# 2_usb.net
KiCad netlist of a schematic drawn in Altium Designer
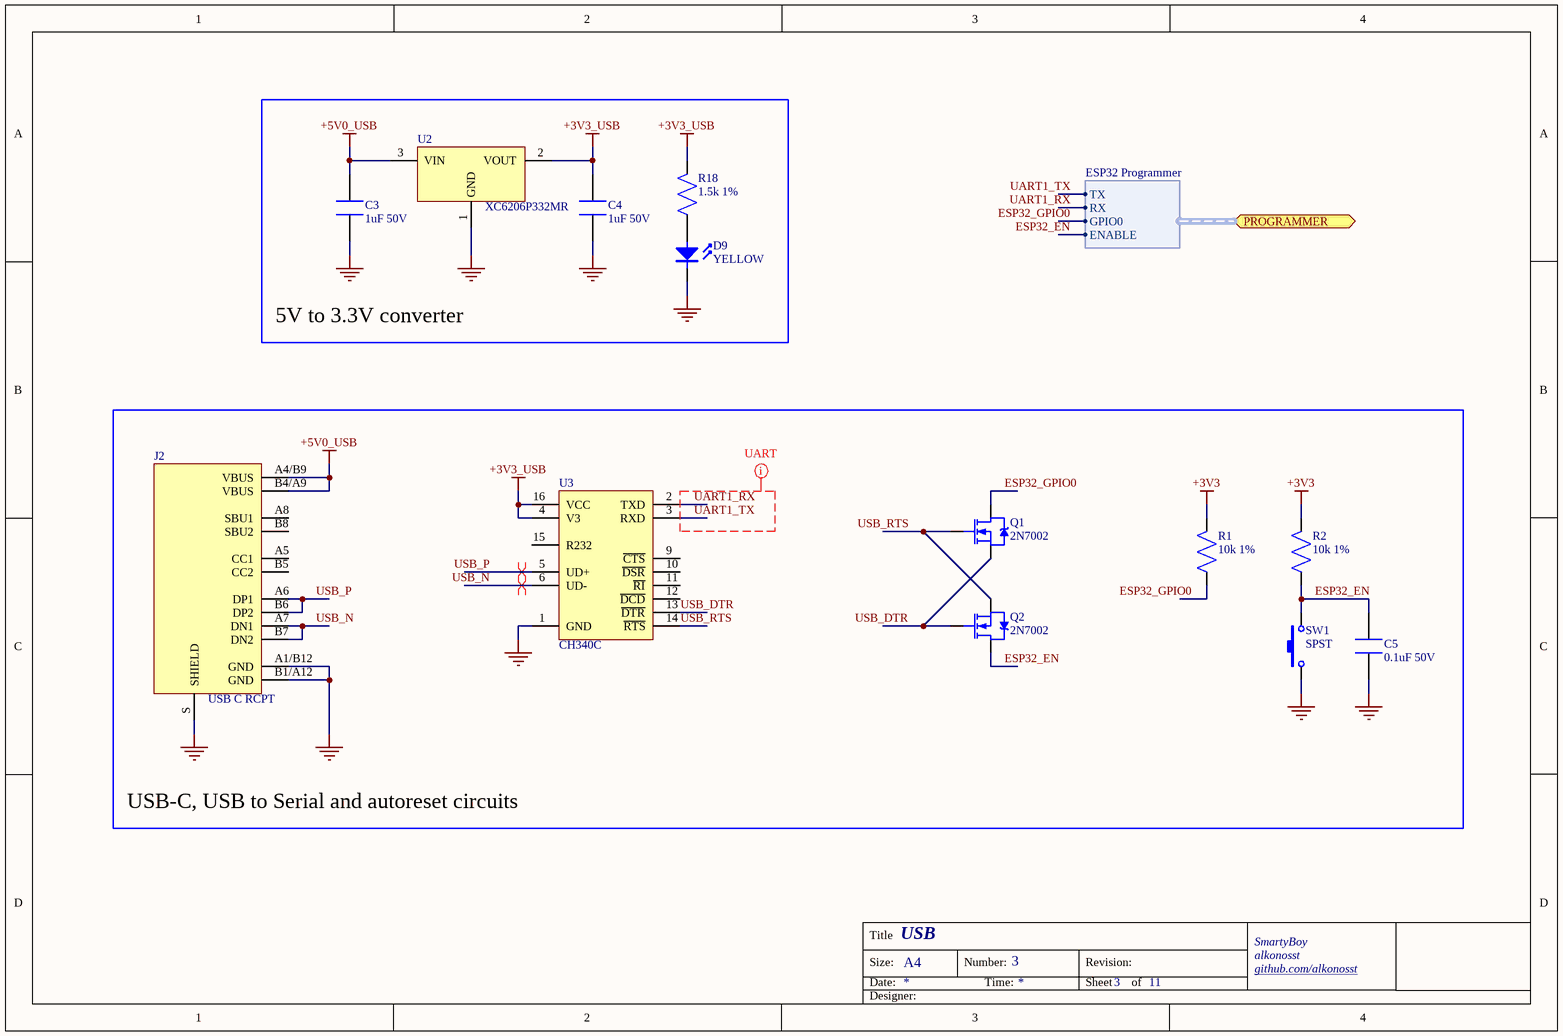
[diagram p0: 2_usb.SchDoc]

(export (version "E")
  (design (tool "Eeschema 10.0.6"))
  (components
    (comp (ref "C3")
      (value "1uF 50V")
      (footprint "C0603")
      (description "X5R ±10% 50V 1uF 0603 Multilayer Ceramic Capacitors MLCC - SMD/SMT")
      (fields (field (name "LCSC PART") "C15849"))
      (libsource (lib "nombre_por_definir") (part "CL10A105KB8NNNC"))
    )
    (comp (ref "C4")
      (value "1uF 50V")
      (footprint "C0603")
      (description "X5R ±10% 50V 1uF 0603 Multilayer Ceramic Capacitors MLCC - SMD/SMT")
      (fields (field (name "LCSC PART") "C15849"))
      (libsource (lib "nombre_por_definir") (part "CL10A105KB8NNNC"))
    )
    (comp (ref "C5")
      (value "0.1uF 50V")
      (footprint "C0603")
      (description "X7R 100nF ±10% 50V 0603 Multilayer Ceramic Capacitors MLCC - SMD/SMT")
      (fields (field (name "LCSC PART") "C14663"))
      (libsource (lib "nombre_por_definir") (part "CC0603KRX7R9BB104"))
    )
    (comp (ref "D9")
      (value "YELLOW")
      (footprint "LED0603-YELLOW")
      (description "Yellow 585.5~591.5nm 0603 Light Emitting Diodes (LED)")
      (fields (field (name "LCSC PART") "C72038"))
      (libsource (lib "nombre_por_definir") (part "19-213/Y2C-CQ2R2L/3T(CY)"))
    )
    (comp (ref "J2")
      (value "USB C RCPT")
      (footprint "USB-TYPE-C-RCPT")
      (description "Receptacle USB Type C 16 Pins")
      (fields (field (name "LCSC PART") "C165948"))
      (libsource (lib "nombre_por_definir") (part "TYPE-C-31-M-12"))
    )
    (comp (ref "Q1")
      (value "2N7002")
      (footprint "SOT-23-3")
      (description "2.5V 250uA 0.115A 60V N Channel 7.5Ω 500mA,10V 0.2W SOT-23(SOT-23-3) MOSFETs")
      (fields (field (name "LCSC PART") "C8545"))
      (libsource (lib "nombre_por_definir") (part "2N7002"))
    )
    (comp (ref "Q2")
      (value "2N7002")
      (footprint "SOT-23-3")
      (description "2.5V 250uA 0.115A 60V N Channel 7.5Ω 500mA,10V 0.2W SOT-23(SOT-23-3) MOSFETs")
      (fields (field (name "LCSC PART") "C8545"))
      (libsource (lib "nombre_por_definir") (part "2N7002"))
    )
    (comp (ref "R1")
      (value "10k 1%")
      (footprint "R0603")
      (description "±1% ±100ppm/℃ 10kΩ 0.1W 0603 Chip Resistor - Surface Mount")
      (fields (field (name "LCSC PART") "C25804"))
      (libsource (lib "nombre_por_definir") (part "0603WAF1002T5E"))
    )
    (comp (ref "R2")
      (value "10k 1%")
      (footprint "R0603")
      (description "±1% ±100ppm/℃ 10kΩ 0.1W 0603 Chip Resistor - Surface Mount")
      (fields (field (name "LCSC PART") "C25804"))
      (libsource (lib "nombre_por_definir") (part "0603WAF1002T5E"))
    )
    (comp (ref "R18")
      (value "1.5k 1%")
      (footprint "R0603")
      (description "1.5kΩ ±1% ±100ppm/℃ 0.1W 0603 Chip Resistor - Surface Mount")
      (fields (field (name "LCSC PART") "C22843"))
      (libsource (lib "nombre_por_definir") (part "0603WAF1501T5E"))
    )
    (comp (ref "SW1")
      (value "SPST")
      (footprint "SW-TS-1187A-B-A-B")
      (description "Top Actuated 50mA @ 12VDC Round Button 160gf SPST SMD Tactile Switches")
      (fields (field (name "LCSC PART") "C318884"))
      (libsource (lib "nombre_por_definir") (part "TS-1187A-B-A-B"))
    )
    (comp (ref "U2")
      (value "XC6206P332MR")
      (footprint "SOT-23-3")
      (description "6V 680mV @ 100mA Fixed 3.3V SOT-23-3L Linear Voltage Regulators (LDO)")
      (fields (field (name "LCSC PART") "C5446"))
      (libsource (lib "nombre_por_definir") (part "XC6206P332MR"))
    )
    (comp (ref "U3")
      (value "CH340C")
      (footprint "SOP-16")
      (description "USB 2.0 Transceiver 2Mbps SOP-16_150mil USB ICs ROHS")
      (fields (field (name "LCSC PART") "C84681"))
      (libsource (lib "nombre_por_definir") (part "CH340C"))
    )
  )
  (nets
    (net (code "3") (name "+3V3") (class "Default")
      (node (ref "R1") (pin "2") (pinfunction "2_2") (pintype "passive"))
      (node (ref "R2") (pin "2") (pinfunction "2_2") (pintype "passive"))
    )
    (net (code "4") (name "+3V3_USB") (class "Default")
      (node (ref "C4") (pin "1") (pinfunction "1_1") (pintype "passive"))
      (node (ref "R18") (pin "2") (pinfunction "2_2") (pintype "passive"))
      (node (ref "U2") (pin "2") (pinfunction "VOUT_2") (pintype "passive"))
      (node (ref "U3") (pin "16") (pinfunction "VCC_16") (pintype "passive"))
      (node (ref "U3") (pin "4") (pinfunction "V3_4") (pintype "passive"))
    )
    (net (code "5") (name "+5V0_USB") (class "Default")
      (node (ref "C3") (pin "1") (pinfunction "1_1") (pintype "passive"))
      (node (ref "J2") (pin "A4/B9") (pinfunction "VBUS_A4/B9") (pintype "passive"))
      (node (ref "J2") (pin "B4/A9") (pinfunction "VBUS_B4/A9") (pintype "passive"))
      (node (ref "U2") (pin "3") (pinfunction "VIN_3") (pintype "passive"))
    )
    (net (code "6") (name "/ESP32_EN") (class "Default")
      (node (ref "C5") (pin "1") (pinfunction "1_1") (pintype "passive"))
      (node (ref "Q2") (pin "3") (pinfunction "D_3") (pintype "passive"))
      (node (ref "R2") (pin "1") (pinfunction "1_1") (pintype "passive"))
      (node (ref "SW1") (pin "2") (pinfunction "2_2") (pintype "passive"))
    )
    (net (code "7") (name "/ESP32_GPIO0") (class "Default")
      (node (ref "Q1") (pin "3") (pinfunction "D_3") (pintype "passive"))
      (node (ref "R1") (pin "1") (pinfunction "1_1") (pintype "passive"))
    )
    (net (code "8") (name "/UART1_RX") (class "Default")
      (node (ref "U3") (pin "2") (pinfunction "TXD_2") (pintype "passive"))
    )
    (net (code "9") (name "/UART1_TX") (class "Default")
      (node (ref "U3") (pin "3") (pinfunction "RXD_3") (pintype "passive"))
    )
    (net (code "10") (name "/USB_DTR") (class "Default")
      (node (ref "Q1") (pin "2") (pinfunction "S_2") (pintype "passive"))
      (node (ref "Q2") (pin "1") (pinfunction "G_1") (pintype "passive"))
      (node (ref "U3") (pin "13") (pinfunction "~{DTR}_13") (pintype "passive"))
    )
    (net (code "11") (name "/USB_N") (class "Default")
      (node (ref "J2") (pin "A7") (pinfunction "DN1_A7") (pintype "passive"))
      (node (ref "J2") (pin "B7") (pinfunction "DN2_B7") (pintype "passive"))
      (node (ref "U3") (pin "6") (pinfunction "UD-_6") (pintype "passive"))
    )
    (net (code "12") (name "/USB_P") (class "Default")
      (node (ref "J2") (pin "A6") (pinfunction "DP1_A6") (pintype "passive"))
      (node (ref "J2") (pin "B6") (pinfunction "DP2_B6") (pintype "passive"))
      (node (ref "U3") (pin "5") (pinfunction "UD+_5") (pintype "passive"))
    )
    (net (code "13") (name "/USB_RTS") (class "Default")
      (node (ref "Q1") (pin "1") (pinfunction "G_1") (pintype "passive"))
      (node (ref "Q2") (pin "2") (pinfunction "S_2") (pintype "passive"))
      (node (ref "U3") (pin "14") (pinfunction "~{RTS}_14") (pintype "passive"))
    )
    (net (code "15") (name "GND") (class "Default")
      (node (ref "C3") (pin "2") (pinfunction "2_2") (pintype "passive"))
      (node (ref "C4") (pin "2") (pinfunction "2_2") (pintype "passive"))
      (node (ref "C5") (pin "2") (pinfunction "2_2") (pintype "passive"))
      (node (ref "D9") (pin "1") (pinfunction "1_1") (pintype "passive"))
      (node (ref "J2") (pin "A1/B12") (pinfunction "GND_A1/B12") (pintype "passive"))
      (node (ref "J2") (pin "B1/A12") (pinfunction "GND_B1/A12") (pintype "passive"))
      (node (ref "J2") (pin "S") (pinfunction "SHIELD_S") (pintype "passive"))
      (node (ref "SW1") (pin "1") (pinfunction "1_1") (pintype "passive"))
      (node (ref "U2") (pin "1") (pinfunction "GND_1") (pintype "passive"))
      (node (ref "U3") (pin "1") (pinfunction "GND_1") (pintype "passive"))
    )
    (net (code "16") (name "Net-(D9-Pad2)") (class "Default")
      (node (ref "D9") (pin "2") (pinfunction "2_2") (pintype "passive"))
      (node (ref "R18") (pin "1") (pinfunction "1_1") (pintype "passive"))
    )
    (net (code "17") (name "unconnected-(J2-CC1-PadA5)") (class "Default")
      (node (ref "J2") (pin "A5") (pinfunction "CC1_A5") (pintype "passive"))
    )
    (net (code "18") (name "unconnected-(J2-CC2-PadB5)") (class "Default")
      (node (ref "J2") (pin "B5") (pinfunction "CC2_B5") (pintype "passive"))
    )
    (net (code "19") (name "unconnected-(J2-SBU1-PadA8)") (class "Default")
      (node (ref "J2") (pin "A8") (pinfunction "SBU1_A8") (pintype "passive"))
    )
    (net (code "20") (name "unconnected-(J2-SBU2-PadB8)") (class "Default")
      (node (ref "J2") (pin "B8") (pinfunction "SBU2_B8") (pintype "passive"))
    )
    (net (code "21") (name "unconnected-(U3-NC1-Pad7)") (class "Default")
      (node (ref "U3") (pin "7") (pinfunction "NC1_7") (pintype "passive"))
    )
    (net (code "22") (name "unconnected-(U3-NC2-Pad8)") (class "Default")
      (node (ref "U3") (pin "8") (pinfunction "NC2_8") (pintype "passive"))
    )
    (net (code "23") (name "unconnected-(U3-R232-Pad15)") (class "Default")
      (node (ref "U3") (pin "15") (pinfunction "R232_15") (pintype "passive"))
    )
    (net (code "24") (name "unconnected-(U3-~{CTS}-Pad9)") (class "Default")
      (node (ref "U3") (pin "9") (pinfunction "~{CTS}_9") (pintype "passive"))
    )
    (net (code "25") (name "unconnected-(U3-~{DCD}-Pad12)") (class "Default")
      (node (ref "U3") (pin "12") (pinfunction "~{DCD}_12") (pintype "passive"))
    )
    (net (code "26") (name "unconnected-(U3-~{DSR}-Pad10)") (class "Default")
      (node (ref "U3") (pin "10") (pinfunction "~{DSR}_10") (pintype "passive"))
    )
    (net (code "27") (name "unconnected-(U3-~{RI}-Pad11)") (class "Default")
      (node (ref "U3") (pin "11") (pinfunction "~{RI}_11") (pintype "passive"))
    )
  )
)
